# 05_CONNECTOR_IN.net
KiCad netlist of a schematic drawn in Altium Designer
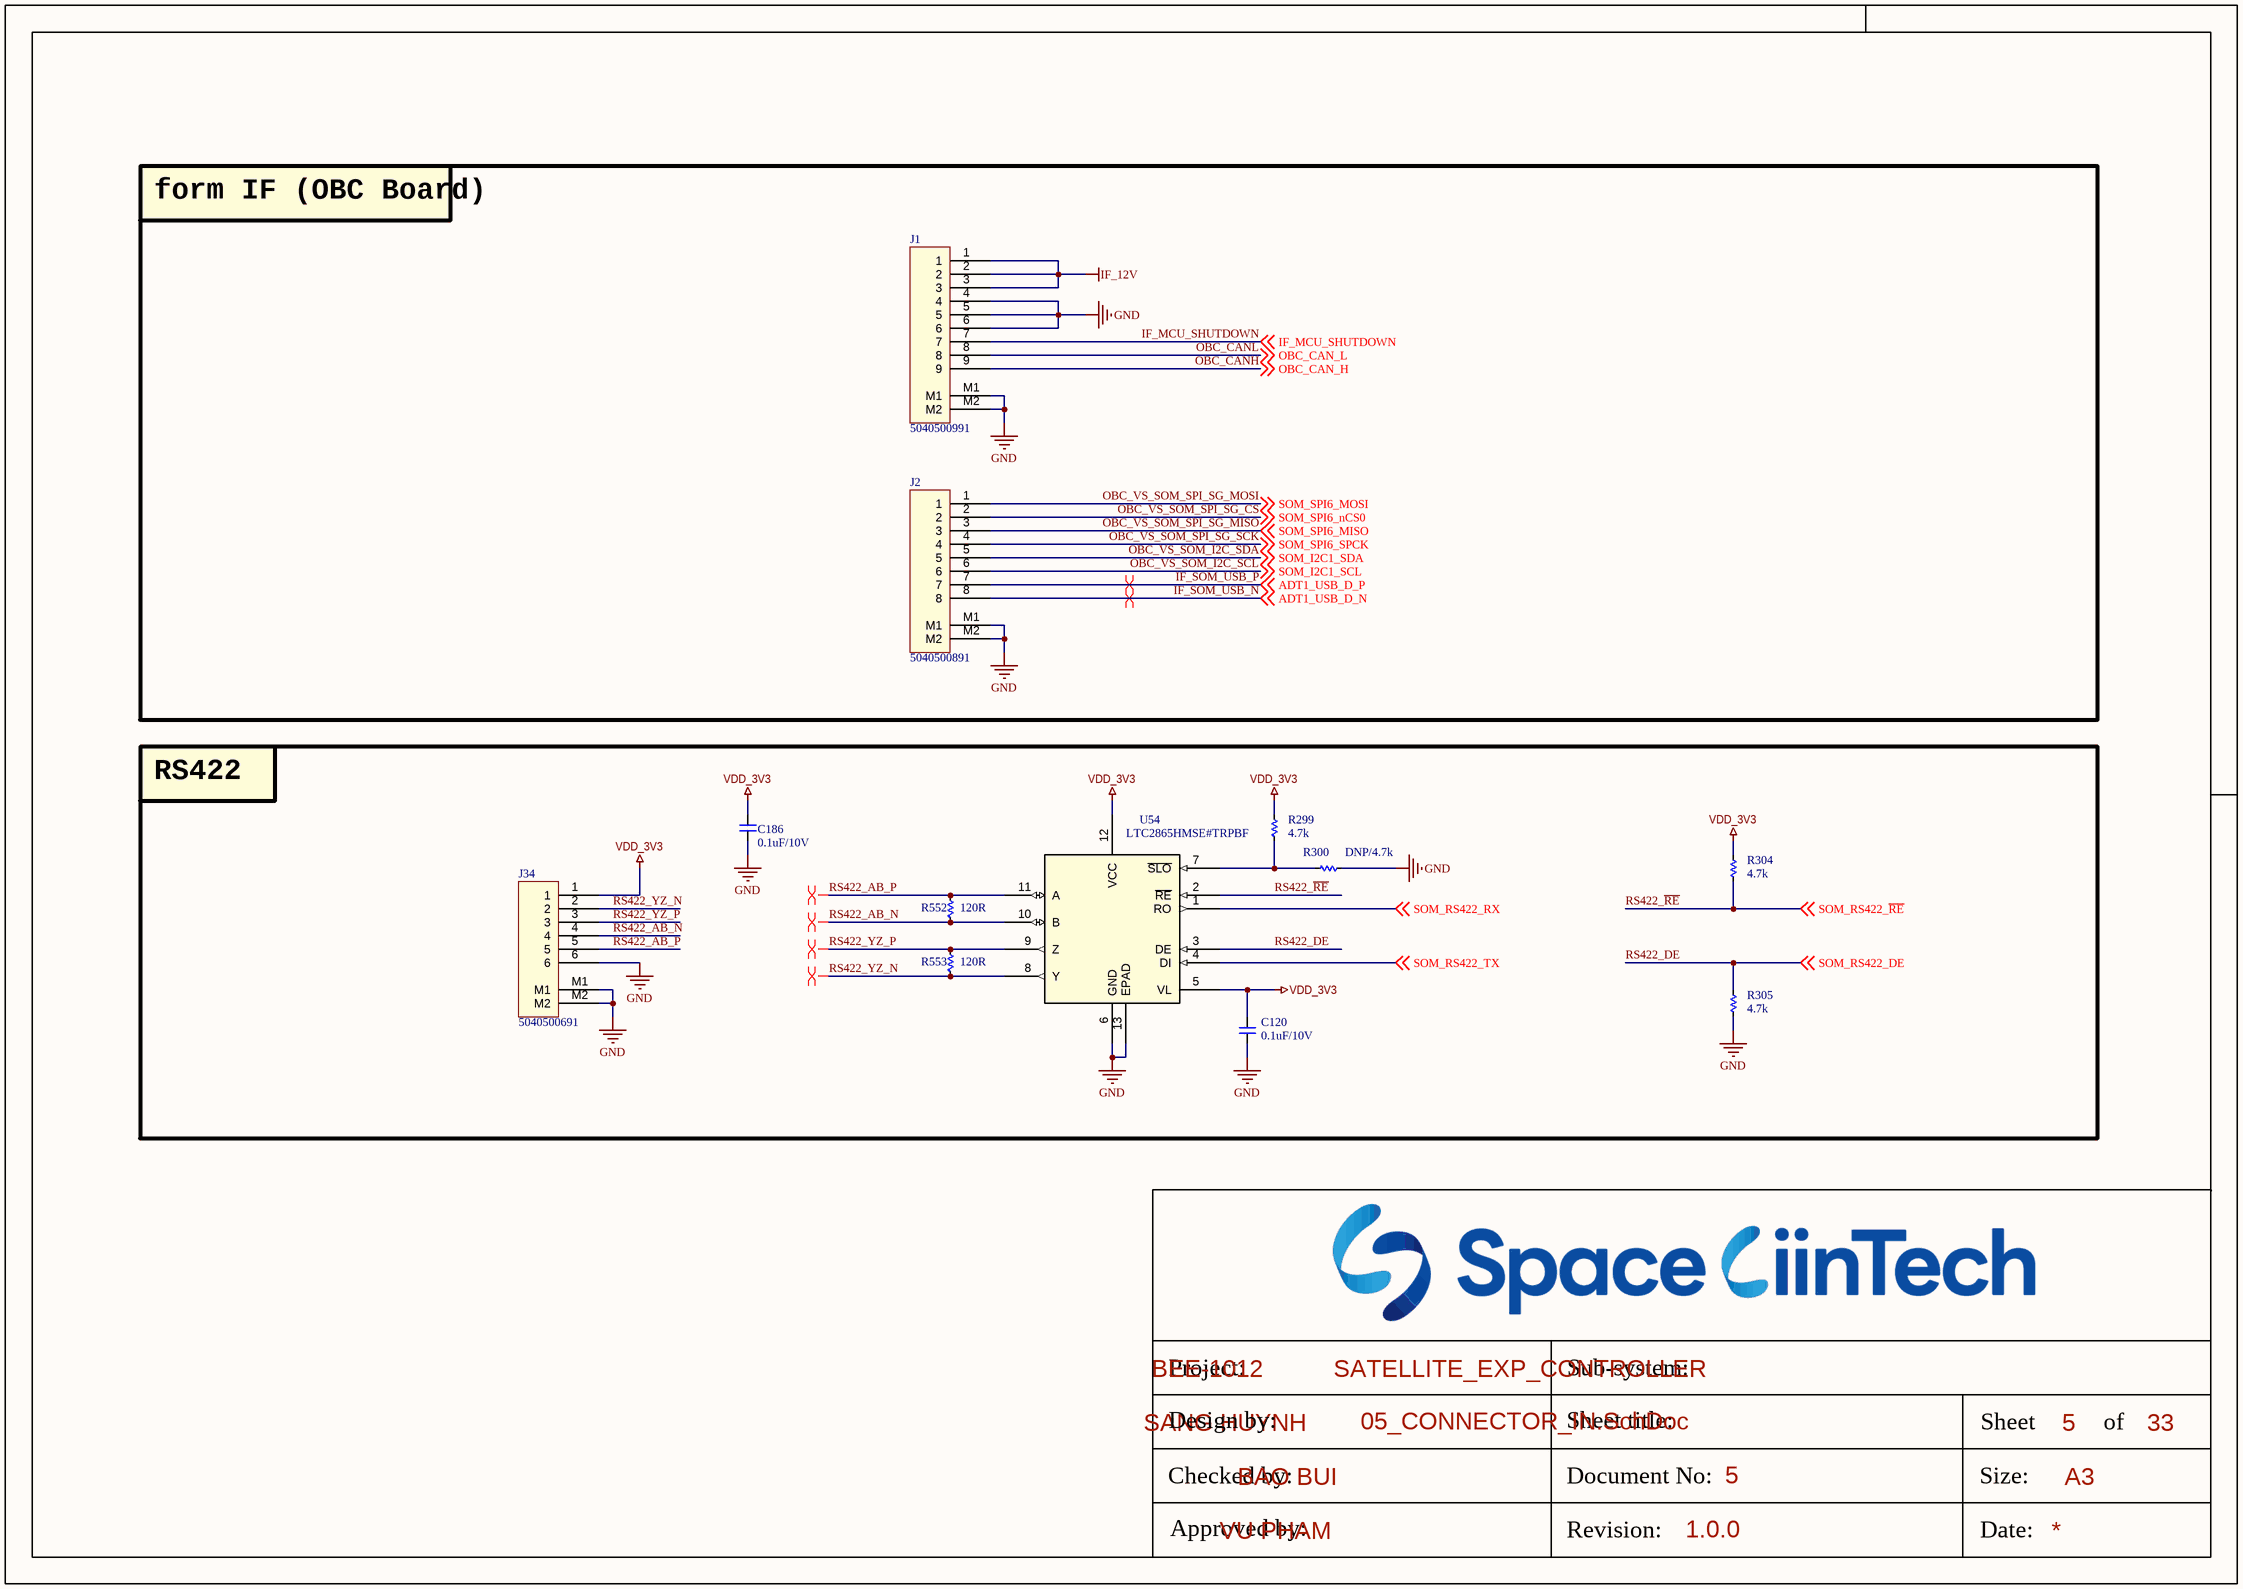
[diagram p0: 05_CONNECTOR_IN.SchDoc]

(export (version "E")
  (design (tool "Eeschema 10.0.6"))
  (components
    (comp (ref "C120")
      (value "0.1uF/10V")
      (footprint "CAP_C_1005X50_L")
      (description "CAP CHIP")
      (libsource (lib "LABLIB") (part "_CAP_C_2"))
    )
    (comp (ref "C186")
      (value "0.1uF/10V")
      (footprint "CAP_C_1005X50_L")
      (description "CAP CHIP")
      (libsource (lib "LABLIB") (part "_CAP_C_2"))
    )
    (comp (ref "J1")
      (value "5040500991")
      (footprint "MOLEX_5040500991")
      (libsource (lib "LABLIB") (part "Header 9x1_2M"))
    )
    (comp (ref "J2")
      (value "5040500891")
      (footprint "MOLEX_5040500891")
      (libsource (lib "LABLIB") (part "Header 8x1_2M"))
    )
    (comp (ref "J34")
      (value "5040500691")
      (footprint "MOLEX_5040500691")
      (libsource (lib "LABLIB") (part "Header 6x1_2M"))
    )
    (comp (ref "R299")
      (value "4.7k")
      (footprint "RES_C_1005x30_L")
      (description "RES")
      (libsource (lib "LABLIB") (part "_RES_B_2"))
    )
    (comp (ref "R300")
      (value "DNP/4.7k")
      (footprint "RES_C_1005x30_L")
      (description "RES")
      (libsource (lib "LABLIB") (part "_RES_B_2"))
    )
    (comp (ref "R304")
      (value "4.7k")
      (footprint "RES_C_1005x30_L")
      (description "RES")
      (libsource (lib "LABLIB") (part "_RES_B_2"))
    )
    (comp (ref "R305")
      (value "4.7k")
      (footprint "RES_C_1005x30_L")
      (description "RES")
      (libsource (lib "LABLIB") (part "_RES_B_2"))
    )
    (comp (ref "R552")
      (value "120R")
      (footprint "RES_C_1005x30_L")
      (description "RES")
      (libsource (lib "LABLIB") (part "_RES_B_2"))
    )
    (comp (ref "R553")
      (value "120R")
      (footprint "RES_C_1005x30_L")
      (description "RES")
      (libsource (lib "LABLIB") (part "_RES_B_2"))
    )
    (comp (ref "U54")
      (value "LTC2865HMSE#TRPBF")
      (footprint "MSOP-12_MSE_LIT")
      (description "Â±60V Fault Protected 3V to 5.5V RS485/RS422 Transceivers")
      (fields (field (name "COPYRIGHT") "Copyright (C) 2025 Ultra Librarian. All rights reserved."))
      (libsource (lib "LABLIB") (part "LTC2865HMSETRPBF"))
    )
  )
  (nets
    (net (code "1") (name "/RS422_AB_N") (class "Default")
      (node (ref "J34") (pin "4") (pinfunction "4_4") (pintype "passive"))
      (node (ref "R552") (pin "2") (pinfunction "2_2") (pintype "passive"))
      (node (ref "U54") (pin "10") (pinfunction "B_10") (pintype "bidirectional"))
    )
    (net (code "2") (name "/RS422_AB_P") (class "Default")
      (node (ref "J34") (pin "5") (pinfunction "5_5") (pintype "passive"))
      (node (ref "R552") (pin "1") (pinfunction "1_1") (pintype "passive"))
      (node (ref "U54") (pin "11") (pinfunction "A_11") (pintype "bidirectional"))
    )
    (net (code "3") (name "/RS422_YZ_N") (class "Default")
      (node (ref "J34") (pin "2") (pinfunction "2_2") (pintype "passive"))
      (node (ref "R553") (pin "2") (pinfunction "2_2") (pintype "passive"))
      (node (ref "U54") (pin "8") (pinfunction "Y_8") (pintype "output"))
    )
    (net (code "4") (name "/RS422_YZ_P") (class "Default")
      (node (ref "J34") (pin "3") (pinfunction "3_3") (pintype "passive"))
      (node (ref "R553") (pin "1") (pinfunction "1_1") (pintype "passive"))
      (node (ref "U54") (pin "9") (pinfunction "Z_9") (pintype "output"))
    )
    (net (code "5") (name "ADT1_USB_D_N") (class "Default")
      (node (ref "J2") (pin "8") (pinfunction "8_8") (pintype "passive"))
    )
    (net (code "6") (name "ADT1_USB_D_P") (class "Default")
      (node (ref "J2") (pin "7") (pinfunction "7_7") (pintype "passive"))
    )
    (net (code "7") (name "GND") (class "Default")
      (node (ref "C120") (pin "1") (pinfunction "1_1") (pintype "passive"))
      (node (ref "C186") (pin "1") (pinfunction "1_1") (pintype "passive"))
      (node (ref "J1") (pin "4") (pinfunction "4_4") (pintype "passive"))
      (node (ref "J1") (pin "5") (pinfunction "5_5") (pintype "passive"))
      (node (ref "J1") (pin "6") (pinfunction "6_6") (pintype "passive"))
      (node (ref "J1") (pin "M1") (pinfunction "M1_M1") (pintype "passive"))
      (node (ref "J1") (pin "M2") (pinfunction "M2_M2") (pintype "passive"))
      (node (ref "J2") (pin "M1") (pinfunction "M1_M1") (pintype "passive"))
      (node (ref "J2") (pin "M2") (pinfunction "M2_M2") (pintype "passive"))
      (node (ref "J34") (pin "6") (pinfunction "6_6") (pintype "passive"))
      (node (ref "J34") (pin "M1") (pinfunction "M1_M1") (pintype "passive"))
      (node (ref "J34") (pin "M2") (pinfunction "M2_M2") (pintype "passive"))
      (node (ref "R300") (pin "2") (pinfunction "2_2") (pintype "passive"))
      (node (ref "R305") (pin "1") (pinfunction "1_1") (pintype "passive"))
      (node (ref "U54") (pin "13") (pinfunction "EPAD_13") (pintype "passive"))
      (node (ref "U54") (pin "6") (pinfunction "GND_6") (pintype "power_in"))
    )
    (net (code "8") (name "IF_12V") (class "Default")
      (node (ref "J1") (pin "1") (pinfunction "1_1") (pintype "passive"))
      (node (ref "J1") (pin "2") (pinfunction "2_2") (pintype "passive"))
      (node (ref "J1") (pin "3") (pinfunction "3_3") (pintype "passive"))
    )
    (net (code "9") (name "IF_MCU_SHUTDOWN") (class "Default")
      (node (ref "J1") (pin "7") (pinfunction "7_7") (pintype "passive"))
    )
    (net (code "10") (name "Net-(U54-~{SLO})") (class "Default")
      (node (ref "R299") (pin "2") (pinfunction "2_2") (pintype "passive"))
      (node (ref "R300") (pin "1") (pinfunction "1_1") (pintype "passive"))
      (node (ref "U54") (pin "7") (pinfunction "~{SLO}_7") (pintype "input"))
    )
    (net (code "11") (name "OBC_CAN_H") (class "Default")
      (node (ref "J1") (pin "9") (pinfunction "9_9") (pintype "passive"))
    )
    (net (code "12") (name "OBC_CAN_L") (class "Default")
      (node (ref "J1") (pin "8") (pinfunction "8_8") (pintype "passive"))
    )
    (net (code "13") (name "SOM_I2C1_SCL") (class "Default")
      (node (ref "J2") (pin "6") (pinfunction "6_6") (pintype "passive"))
    )
    (net (code "14") (name "SOM_I2C1_SDA") (class "Default")
      (node (ref "J2") (pin "5") (pinfunction "5_5") (pintype "passive"))
    )
    (net (code "15") (name "SOM_RS422_DE") (class "Default")
      (node (ref "R305") (pin "2") (pinfunction "2_2") (pintype "passive"))
      (node (ref "U54") (pin "3") (pinfunction "DE_3") (pintype "input"))
    )
    (net (code "16") (name "SOM_RS422_RX") (class "Default")
      (node (ref "U54") (pin "1") (pinfunction "RO_1") (pintype "output"))
    )
    (net (code "17") (name "SOM_RS422_TX") (class "Default")
      (node (ref "U54") (pin "4") (pinfunction "DI_4") (pintype "input"))
    )
    (net (code "18") (name "SOM_RS422_~{RE}") (class "Default")
      (node (ref "R304") (pin "2") (pinfunction "2_2") (pintype "passive"))
      (node (ref "U54") (pin "2") (pinfunction "~{RE}_2") (pintype "input"))
    )
    (net (code "19") (name "SOM_SPI6_MISO") (class "Default")
      (node (ref "J2") (pin "3") (pinfunction "3_3") (pintype "passive"))
    )
    (net (code "20") (name "SOM_SPI6_MOSI") (class "Default")
      (node (ref "J2") (pin "1") (pinfunction "1_1") (pintype "passive"))
    )
    (net (code "21") (name "SOM_SPI6_SPCK") (class "Default")
      (node (ref "J2") (pin "4") (pinfunction "4_4") (pintype "passive"))
    )
    (net (code "22") (name "SOM_SPI6_nCS0") (class "Default")
      (node (ref "J2") (pin "2") (pinfunction "2_2") (pintype "passive"))
    )
    (net (code "23") (name "VDD_3V3") (class "Default")
      (node (ref "C120") (pin "2") (pinfunction "2_2") (pintype "passive"))
      (node (ref "C186") (pin "2") (pinfunction "2_2") (pintype "passive"))
      (node (ref "J34") (pin "1") (pinfunction "1_1") (pintype "passive"))
      (node (ref "R299") (pin "1") (pinfunction "1_1") (pintype "passive"))
      (node (ref "R304") (pin "1") (pinfunction "1_1") (pintype "passive"))
      (node (ref "U54") (pin "12") (pinfunction "VCC_12") (pintype "power_in"))
      (node (ref "U54") (pin "5") (pinfunction "VL_5") (pintype "power_in"))
    )
  )
)
